# STM32G474RBT6.net
KiCad netlist of a schematic drawn in EasyEDA Pro
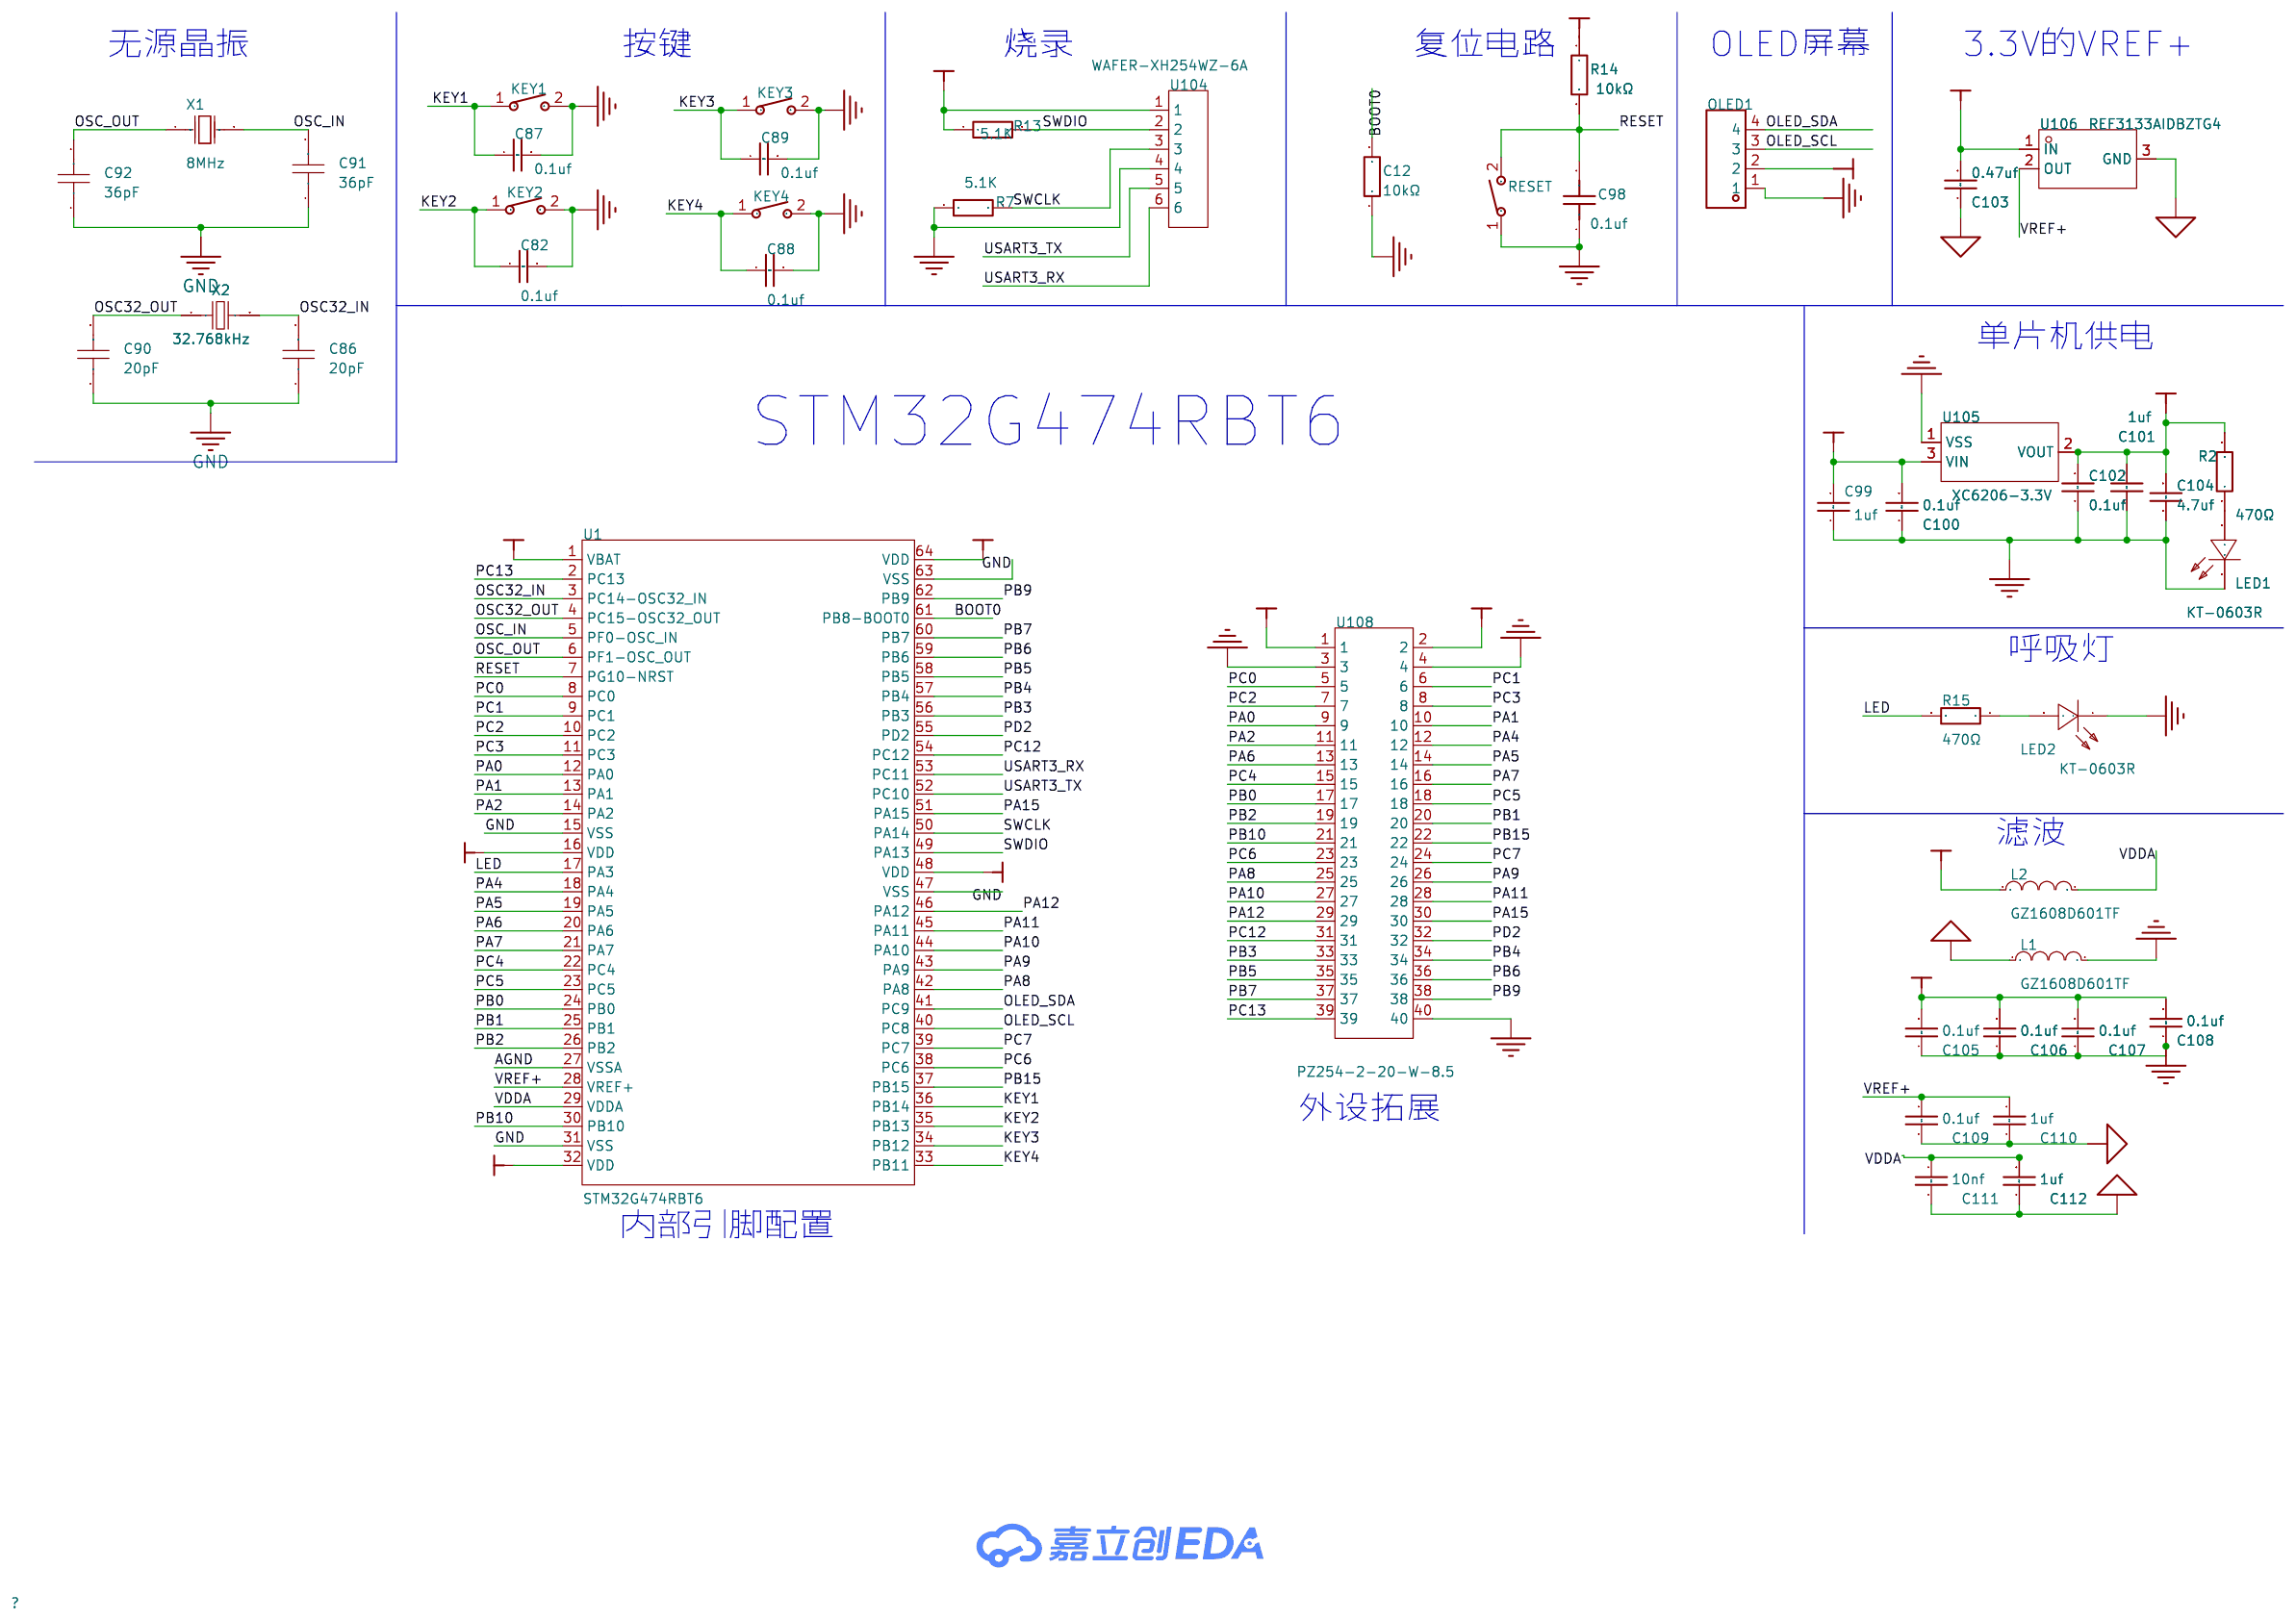
[diagram p0: schematic sheet]

(export (version "E")
  (design (tool "Eeschema 10.0.6"))
  (components
    (comp (ref "C12")
      (value "10kΩ")
      (footprint "easyedapro:R0805")
      (fields
        (field (name "Manufacturer Part") "0805W8F1002T5E")
        (field (name "Manufacturer") "UNI-ROYAL(厚声)")
      )
      (libsource (lib "easyedapro") (part "0805W8F1002T5E"))
    )
    (comp (ref "C82")
      (value "0.1uf")
      (footprint "easyedapro:C0603")
      (libsource (lib "easyedapro") (part "C0603"))
    )
    (comp (ref "C86")
      (value "20pF")
      (footprint "easyedapro:C0603")
      (description "容值:47pF;精度:±5%;额定电压:100V;温度系数:C0G;")
      (fields
        (field (name "Manufacturer Part") "CAI0603C0G470J101JT")
        (field (name "Manufacturer") "HRE(芯声)")
      )
      (libsource (lib "easyedapro") (part "CAI0603C0G470J101JT"))
    )
    (comp (ref "C87")
      (value "0.1uf")
      (footprint "easyedapro:C0603")
      (libsource (lib "easyedapro") (part "C0603"))
    )
    (comp (ref "C88")
      (value "0.1uf")
      (footprint "easyedapro:C0603")
      (libsource (lib "easyedapro") (part "C0603"))
    )
    (comp (ref "C89")
      (value "0.1uf")
      (footprint "easyedapro:C0603")
      (libsource (lib "easyedapro") (part "C0603"))
    )
    (comp (ref "C90")
      (value "20pF")
      (footprint "easyedapro:C0603")
      (description "容值:47pF;精度:±5%;额定电压:100V;温度系数:C0G;")
      (fields
        (field (name "Manufacturer Part") "CAI0603C0G470J101JT")
        (field (name "Manufacturer") "HRE(芯声)")
      )
      (libsource (lib "easyedapro") (part "CAI0603C0G470J101JT"))
    )
    (comp (ref "C91")
      (value "36pF")
      (footprint "easyedapro:C0603")
      (description "容值:47pF;精度:±5%;额定电压:100V;温度系数:C0G;")
      (fields
        (field (name "Manufacturer Part") "CAI0603C0G470J101JT")
        (field (name "Manufacturer") "HRE(芯声)")
      )
      (libsource (lib "easyedapro") (part "CAI0603C0G470J101JT"))
    )
    (comp (ref "C92")
      (value "36pF")
      (footprint "easyedapro:C0603")
      (description "容值:47pF;精度:±5%;额定电压:100V;温度系数:C0G;")
      (fields
        (field (name "Manufacturer Part") "CAI0603C0G470J101JT")
        (field (name "Manufacturer") "HRE(芯声)")
      )
      (libsource (lib "easyedapro") (part "CAI0603C0G470J101JT"))
    )
    (comp (ref "C98") (value "0.1uf") (footprint "easyedapro:电容") (libsource (lib "easyedapro") (part "电容")))
    (comp (ref "C99")
      (value "1uf")
      (footprint "easyedapro:C0603")
      (libsource (lib "easyedapro") (part "C0603"))
    )
    (comp (ref "C100")
      (value "0.1uf")
      (footprint "easyedapro:C0603")
      (libsource (lib "easyedapro") (part "C0603"))
    )
    (comp (ref "C101")
      (value "1uf")
      (footprint "easyedapro:C0603")
      (libsource (lib "easyedapro") (part "C0603"))
    )
    (comp (ref "C102")
      (value "0.1uf")
      (footprint "easyedapro:C0603")
      (libsource (lib "easyedapro") (part "C0603"))
    )
    (comp (ref "C103")
      (value "0.47uf")
      (footprint "easyedapro:C0603")
      (libsource (lib "easyedapro") (part "C0603"))
    )
    (comp (ref "C104")
      (value "4.7uf")
      (footprint "easyedapro:C0603")
      (libsource (lib "easyedapro") (part "C0603"))
    )
    (comp (ref "C105")
      (value "0.1uf")
      (footprint "easyedapro:C0603")
      (libsource (lib "easyedapro") (part "C0603"))
    )
    (comp (ref "C106")
      (value "0.1uf")
      (footprint "easyedapro:C0603")
      (libsource (lib "easyedapro") (part "C0603"))
    )
    (comp (ref "C107")
      (value "0.1uf")
      (footprint "easyedapro:C0603")
      (libsource (lib "easyedapro") (part "C0603"))
    )
    (comp (ref "C108")
      (value "0.1uf")
      (footprint "easyedapro:C0603")
      (libsource (lib "easyedapro") (part "C0603"))
    )
    (comp (ref "C109")
      (value "0.1uf")
      (footprint "easyedapro:C0603")
      (libsource (lib "easyedapro") (part "C0603"))
    )
    (comp (ref "C110")
      (value "1uf")
      (footprint "easyedapro:C0603")
      (libsource (lib "easyedapro") (part "C0603"))
    )
    (comp (ref "C111")
      (value "10nf")
      (footprint "easyedapro:C0603")
      (libsource (lib "easyedapro") (part "C0603"))
    )
    (comp (ref "C112")
      (value "1uf")
      (footprint "easyedapro:C0603")
      (libsource (lib "easyedapro") (part "C0603"))
    )
    (comp (ref "KEY1")
      (value "TS6643WS 250gf 072")
      (footprint "easyedapro:SW-SMD_L6.0-W6.0-P6.00-LS6.8")
      (fields (field (name "Manufacturer") "SHOU HAN(首韩)"))
      (libsource (lib "easyedapro") (part "TS6643WS 250GF 072"))
    )
    (comp (ref "KEY2")
      (value "TS6643WS 250gf 072")
      (footprint "easyedapro:SW-SMD_L6.0-W6.0-P6.00-LS6.8")
      (fields (field (name "Manufacturer") "SHOU HAN(首韩)"))
      (libsource (lib "easyedapro") (part "TS6643WS 250GF 072"))
    )
    (comp (ref "KEY3")
      (value "TS6643WS 250gf 072")
      (footprint "easyedapro:SW-SMD_L6.0-W6.0-P6.00-LS6.8")
      (fields (field (name "Manufacturer") "SHOU HAN(首韩)"))
      (libsource (lib "easyedapro") (part "TS6643WS 250GF 072"))
    )
    (comp (ref "KEY4")
      (value "TS6643WS 250gf 072")
      (footprint "easyedapro:SW-SMD_L6.0-W6.0-P6.00-LS6.8")
      (fields (field (name "Manufacturer") "SHOU HAN(首韩)"))
      (libsource (lib "easyedapro") (part "TS6643WS 250GF 072"))
    )
    (comp (ref "L1")
      (value "GZ1608D601TF")
      (footprint "easyedapro:L0603")
      (description "阻抗@频率:600Ω@100MHz;误差:±25%;直流电阻(DCR):450mΩ;")
      (fields (field (name "Manufacturer") "Sunlord(顺络)"))
      (libsource (lib "easyedapro") (part "GZ1608D601TF"))
    )
    (comp (ref "L2")
      (value "GZ1608D601TF")
      (footprint "easyedapro:L0603")
      (description "阻抗@频率:600Ω@100MHz;误差:±25%;直流电阻(DCR):450mΩ;")
      (fields (field (name "Manufacturer") "Sunlord(顺络)"))
      (libsource (lib "easyedapro") (part "GZ1608D601TF"))
    )
    (comp (ref "LED1")
      (value "KT-0603R")
      (footprint "easyedapro:LED0603-RD")
      (fields (field (name "Manufacturer") "KENTO"))
      (libsource (lib "easyedapro") (part "KT-0603R"))
    )
    (comp (ref "LED2")
      (value "KT-0603R")
      (footprint "easyedapro:LED0603-RD")
      (fields (field (name "Manufacturer") "KENTO"))
      (libsource (lib "easyedapro") (part "KT-0603R"))
    )
    (comp (ref "OLED1")
      (value "2.54-1*4P母")
      (footprint "easyedapro:HDR-TH_4P-P2.54-V-F")
      (fields (field (name "Manufacturer") "BOOMELE(博穆精密)"))
      (libsource (lib "easyedapro") (part "2.54-1*4P母"))
    )
    (comp (ref "R2")
      (value "470Ω")
      (footprint "easyedapro:R0805")
      (description "电阻类型:厚膜电阻;阻值:5.1kΩ;精度:±1%;功率:125mW;最大工作电压:150V;温度系数:±100ppm/℃;")
      (fields
        (field (name "Manufacturer Part") "0805W8F5101T5E")
        (field (name "Manufacturer") "UNI-ROYAL(厚声)")
      )
      (libsource (lib "easyedapro") (part "0805W8F5101T5E"))
    )
    (comp (ref "R7") (value "5.1K") (footprint "easyedapro:电阻") (libsource (lib "easyedapro") (part "电阻")))
    (comp (ref "R13") (value "5.1K") (footprint "easyedapro:电阻") (libsource (lib "easyedapro") (part "电阻")))
    (comp (ref "R14") (value "10kΩ") (footprint "easyedapro:电阻") (libsource (lib "easyedapro") (part "电阻")))
    (comp (ref "R15")
      (value "470Ω")
      (footprint "easyedapro:R0805")
      (description "电阻类型:厚膜电阻;阻值:5.1kΩ;精度:±1%;功率:125mW;最大工作电压:150V;温度系数:±100ppm/℃;")
      (fields
        (field (name "Manufacturer Part") "0805W8F5101T5E")
        (field (name "Manufacturer") "UNI-ROYAL(厚声)")
      )
      (libsource (lib "easyedapro") (part "0805W8F5101T5E"))
    )
    (comp (ref "RESET")
      (value "TS6643WS 250gf 072")
      (footprint "easyedapro:SW-SMD_L6.0-W6.0-P6.00-LS6.8")
      (fields (field (name "Manufacturer") "SHOU HAN(首韩)"))
      (libsource (lib "easyedapro") (part "TS6643WS 250GF 072"))
    )
    (comp (ref "U1")
      (value "STM32G474RBT6")
      (footprint "easyedapro:LQFP-64_L10.0-W10.0-P0.50-LS12.0-BL")
      (description "CPU内核:ARM-M4;CPU最大主频:170MHz;应用领域:-;")
      (fields (field (name "Manufacturer") "ST(意法半导体)"))
      (libsource (lib "easyedapro") (part "STM32G474RBT6"))
    )
    (comp (ref "U104")
      (value "WAFER-XH254WZ-6A")
      (footprint "easyedapro:CONN-TH_6P-P2.50_WAFER-XH254WZ-6A")
      (description "插针结构:1x6P;间距:2.54mm;安装方式:弯插;参考系列:XH;总PIN数:6P;排数:1;每排PIN数:6;额定电流:3A;触头材质:黄铜;工作温度:-25°C~+85°C;")
      (fields (field (name "Manufacturer") "HANBO(汉博)"))
      (libsource (lib "easyedapro") (part "WAFER-XH254WZ-6A"))
    )
    (comp (ref "U105")
      (value "XC6206-3.3V")
      (footprint "easyedapro:SSOT-3_L2.9-W1.6-P0.95-LS2.8-BR")
      (description "输出类型:固定;工作电压:6V;输出电压:3.3V;输出电流:250mA;电源纹波抑制比(PSRR):-;输出极性:正极;")
      (fields (field (name "Manufacturer") "YONGYUTAI(永裕泰)"))
      (libsource (lib "easyedapro") (part "XC6206-3.3V"))
    )
    (comp (ref "U106")
      (value "REF3133AIDBZTG4")
      (footprint "easyedapro:SOT-23-3_L2.9-W1.4-0.95-LS2.5-BR")
      (description "输出类型:固定;工作电压:3.35V~5.5V;输出电压:3.3V;输出电流:10mA;精度:±0.2%;")
      (fields (field (name "Manufacturer") "TI(德州仪器)"))
      (libsource (lib "easyedapro") (part "REF3133AIDBZTG4"))
    )
    (comp (ref "U108")
      (value "PZ254-2-20-W-8.5")
      (footprint "easyedapro:HDR-TH_40P-P2.54-H-M-R2-C20-S2.54-W12.9-N")
      (fields (field (name "Manufacturer") "HCTL(华灿天禄)"))
      (libsource (lib "easyedapro") (part "PZ254-2-20-W-8.5KK"))
    )
    (comp (ref "X1")
      (value "8MHz")
      (footprint "easyedapro:CRYSTAL-SMD_L5.0-W3.2")
      (description "晶振类型:贴片晶振;频率:8MHz;常温频差:±10ppm;负载电容:20pF;频率稳定度:±20ppm;")
      (fields (field (name "Manufacturer Part") "X50328MSB2GI") (field (name "Manufacturer") "YXC(扬兴晶振)"))
      (libsource (lib "easyedapro") (part "X50328MSB2GI"))
    )
    (comp (ref "X2")
      (value "32.768kHz")
      (footprint "easyedapro:FC-135R_L3.2-W1.5")
      (description "晶振类型:贴片无源晶振;频率:32.768kHz;频率公差:±20ppm;频率稳定度:-;负载电容:12.5pF;等效串联电阻(ESR):70kΩ;工作温度:-40~+85;")
      (fields (field (name "Manufacturer Part") "Q13FC1350000400") (field (name "Manufacturer") "EPSON(爱普生)"))
      (libsource (lib "easyedapro") (part "Q13FC1350000400"))
    )
  )
  (nets
    (net (code "1") (name "/BOOT0") (class "Default")
      (node (ref "C12") (pin "2") (pinfunction "2_2") (pintype "input"))
      (node (ref "U1") (pin "61") (pinfunction "PB8-BOOT0_61") (pintype "unspecified"))
    )
    (net (code "2") (name "/KEY1") (class "Default")
      (node (ref "C87") (pin "1") (pinfunction "1_1") (pintype "input"))
      (node (ref "KEY1") (pin "1") (pinfunction "1_1") (pintype "unspecified"))
      (node (ref "U1") (pin "36") (pinfunction "PB14_36") (pintype "unspecified"))
    )
    (net (code "3") (name "/KEY2") (class "Default")
      (node (ref "C82") (pin "1") (pinfunction "1_1") (pintype "input"))
      (node (ref "KEY2") (pin "1") (pinfunction "1_1") (pintype "unspecified"))
      (node (ref "U1") (pin "35") (pinfunction "PB13_35") (pintype "unspecified"))
    )
    (net (code "4") (name "/KEY3") (class "Default")
      (node (ref "C89") (pin "1") (pinfunction "1_1") (pintype "input"))
      (node (ref "KEY3") (pin "1") (pinfunction "1_1") (pintype "unspecified"))
      (node (ref "U1") (pin "34") (pinfunction "PB12_34") (pintype "unspecified"))
    )
    (net (code "5") (name "/KEY4") (class "Default")
      (node (ref "C88") (pin "1") (pinfunction "1_1") (pintype "input"))
      (node (ref "KEY4") (pin "1") (pinfunction "1_1") (pintype "unspecified"))
      (node (ref "U1") (pin "33") (pinfunction "PB11_33") (pintype "unspecified"))
    )
    (net (code "6") (name "/LED") (class "Default")
      (node (ref "R15") (pin "2") (pinfunction "2_2") (pintype "input"))
      (node (ref "U1") (pin "17") (pinfunction "PA3_17") (pintype "unspecified"))
    )
    (net (code "7") (name "/OLED_SCL") (class "Default")
      (node (ref "OLED1") (pin "3") (pinfunction "3_3") (pintype "unspecified"))
      (node (ref "U1") (pin "40") (pinfunction "PC8_40") (pintype "unspecified"))
    )
    (net (code "8") (name "/OLED_SDA") (class "Default")
      (node (ref "OLED1") (pin "4") (pinfunction "4_4") (pintype "unspecified"))
      (node (ref "U1") (pin "41") (pinfunction "PC9_41") (pintype "unspecified"))
    )
    (net (code "9") (name "/OSC32_IN") (class "Default")
      (node (ref "C86") (pin "2") (pinfunction "2_2") (pintype "unspecified"))
      (node (ref "U1") (pin "3") (pinfunction "PC14-OSC32_IN_3") (pintype "unspecified"))
      (node (ref "X2") (pin "2") (pinfunction "2_2") (pintype "input"))
    )
    (net (code "10") (name "/OSC32_OUT") (class "Default")
      (node (ref "C90") (pin "2") (pinfunction "2_2") (pintype "unspecified"))
      (node (ref "U1") (pin "4") (pinfunction "PC15-OSC32_OUT_4") (pintype "unspecified"))
      (node (ref "X2") (pin "1") (pinfunction "1_1") (pintype "input"))
    )
    (net (code "11") (name "/OSC_IN") (class "Default")
      (node (ref "C91") (pin "2") (pinfunction "2_2") (pintype "unspecified"))
      (node (ref "U1") (pin "5") (pinfunction "PF0-OSC_IN_5") (pintype "unspecified"))
      (node (ref "X1") (pin "2") (pinfunction "OSC2_2") (pintype "input"))
    )
    (net (code "12") (name "/OSC_OUT") (class "Default")
      (node (ref "C92") (pin "2") (pinfunction "2_2") (pintype "unspecified"))
      (node (ref "U1") (pin "6") (pinfunction "PF1-OSC_OUT_6") (pintype "unspecified"))
      (node (ref "X1") (pin "1") (pinfunction "OSC1_1") (pintype "input"))
    )
    (net (code "13") (name "/PA0") (class "Default")
      (node (ref "U1") (pin "12") (pinfunction "PA0_12") (pintype "unspecified"))
      (node (ref "U108") (pin "9") (pinfunction "9_9") (pintype "unspecified"))
    )
    (net (code "14") (name "/PA1") (class "Default")
      (node (ref "U1") (pin "13") (pinfunction "PA1_13") (pintype "unspecified"))
      (node (ref "U108") (pin "10") (pinfunction "10_10") (pintype "unspecified"))
    )
    (net (code "15") (name "/PA2") (class "Default")
      (node (ref "U1") (pin "14") (pinfunction "PA2_14") (pintype "unspecified"))
      (node (ref "U108") (pin "11") (pinfunction "11_11") (pintype "unspecified"))
    )
    (net (code "16") (name "/PA4") (class "Default")
      (node (ref "U1") (pin "18") (pinfunction "PA4_18") (pintype "unspecified"))
      (node (ref "U108") (pin "12") (pinfunction "12_12") (pintype "unspecified"))
    )
    (net (code "17") (name "/PA5") (class "Default")
      (node (ref "U1") (pin "19") (pinfunction "PA5_19") (pintype "unspecified"))
      (node (ref "U108") (pin "14") (pinfunction "14_14") (pintype "unspecified"))
    )
    (net (code "18") (name "/PA6") (class "Default")
      (node (ref "U1") (pin "20") (pinfunction "PA6_20") (pintype "unspecified"))
      (node (ref "U108") (pin "13") (pinfunction "13_13") (pintype "unspecified"))
    )
    (net (code "19") (name "/PA7") (class "Default")
      (node (ref "U1") (pin "21") (pinfunction "PA7_21") (pintype "unspecified"))
      (node (ref "U108") (pin "16") (pinfunction "16_16") (pintype "unspecified"))
    )
    (net (code "20") (name "/PA8") (class "Default")
      (node (ref "U1") (pin "42") (pinfunction "PA8_42") (pintype "unspecified"))
      (node (ref "U108") (pin "25") (pinfunction "25_25") (pintype "unspecified"))
    )
    (net (code "21") (name "/PA9") (class "Default")
      (node (ref "U1") (pin "43") (pinfunction "PA9_43") (pintype "unspecified"))
      (node (ref "U108") (pin "26") (pinfunction "26_26") (pintype "unspecified"))
    )
    (net (code "22") (name "/PA10") (class "Default")
      (node (ref "U1") (pin "44") (pinfunction "PA10_44") (pintype "unspecified"))
      (node (ref "U108") (pin "27") (pinfunction "27_27") (pintype "unspecified"))
    )
    (net (code "23") (name "/PA11") (class "Default")
      (node (ref "U1") (pin "45") (pinfunction "PA11_45") (pintype "unspecified"))
      (node (ref "U108") (pin "28") (pinfunction "28_28") (pintype "unspecified"))
    )
    (net (code "24") (name "/PA12") (class "Default")
      (node (ref "U1") (pin "46") (pinfunction "PA12_46") (pintype "unspecified"))
      (node (ref "U108") (pin "29") (pinfunction "29_29") (pintype "unspecified"))
    )
    (net (code "25") (name "/PA15") (class "Default")
      (node (ref "U1") (pin "51") (pinfunction "PA15_51") (pintype "unspecified"))
      (node (ref "U108") (pin "30") (pinfunction "30_30") (pintype "unspecified"))
    )
    (net (code "26") (name "/PB0") (class "Default")
      (node (ref "U1") (pin "24") (pinfunction "PB0_24") (pintype "unspecified"))
      (node (ref "U108") (pin "17") (pinfunction "17_17") (pintype "unspecified"))
    )
    (net (code "27") (name "/PB1") (class "Default")
      (node (ref "U1") (pin "25") (pinfunction "PB1_25") (pintype "unspecified"))
      (node (ref "U108") (pin "20") (pinfunction "20_20") (pintype "unspecified"))
    )
    (net (code "28") (name "/PB2") (class "Default")
      (node (ref "U1") (pin "26") (pinfunction "PB2_26") (pintype "unspecified"))
      (node (ref "U108") (pin "19") (pinfunction "19_19") (pintype "unspecified"))
    )
    (net (code "29") (name "/PB3") (class "Default")
      (node (ref "U1") (pin "56") (pinfunction "PB3_56") (pintype "unspecified"))
      (node (ref "U108") (pin "33") (pinfunction "33_33") (pintype "unspecified"))
    )
    (net (code "30") (name "/PB4") (class "Default")
      (node (ref "U1") (pin "57") (pinfunction "PB4_57") (pintype "unspecified"))
      (node (ref "U108") (pin "34") (pinfunction "34_34") (pintype "unspecified"))
    )
    (net (code "31") (name "/PB5") (class "Default")
      (node (ref "U1") (pin "58") (pinfunction "PB5_58") (pintype "unspecified"))
      (node (ref "U108") (pin "35") (pinfunction "35_35") (pintype "unspecified"))
    )
    (net (code "32") (name "/PB6") (class "Default")
      (node (ref "U1") (pin "59") (pinfunction "PB6_59") (pintype "unspecified"))
      (node (ref "U108") (pin "36") (pinfunction "36_36") (pintype "unspecified"))
    )
    (net (code "33") (name "/PB7") (class "Default")
      (node (ref "U1") (pin "60") (pinfunction "PB7_60") (pintype "unspecified"))
      (node (ref "U108") (pin "37") (pinfunction "37_37") (pintype "unspecified"))
    )
    (net (code "34") (name "/PB9") (class "Default")
      (node (ref "U1") (pin "62") (pinfunction "PB9_62") (pintype "unspecified"))
      (node (ref "U108") (pin "38") (pinfunction "38_38") (pintype "unspecified"))
    )
    (net (code "35") (name "/PB10") (class "Default")
      (node (ref "U1") (pin "30") (pinfunction "PB10_30") (pintype "unspecified"))
      (node (ref "U108") (pin "21") (pinfunction "21_21") (pintype "unspecified"))
    )
    (net (code "36") (name "/PB15") (class "Default")
      (node (ref "U1") (pin "37") (pinfunction "PB15_37") (pintype "unspecified"))
      (node (ref "U108") (pin "22") (pinfunction "22_22") (pintype "unspecified"))
    )
    (net (code "37") (name "/PC0") (class "Default")
      (node (ref "U1") (pin "8") (pinfunction "PC0_8") (pintype "unspecified"))
      (node (ref "U108") (pin "5") (pinfunction "5_5") (pintype "unspecified"))
    )
    (net (code "38") (name "/PC1") (class "Default")
      (node (ref "U1") (pin "9") (pinfunction "PC1_9") (pintype "unspecified"))
      (node (ref "U108") (pin "6") (pinfunction "6_6") (pintype "unspecified"))
    )
    (net (code "39") (name "/PC2") (class "Default")
      (node (ref "U1") (pin "10") (pinfunction "PC2_10") (pintype "unspecified"))
      (node (ref "U108") (pin "7") (pinfunction "7_7") (pintype "unspecified"))
    )
    (net (code "40") (name "/PC3") (class "Default")
      (node (ref "U1") (pin "11") (pinfunction "PC3_11") (pintype "unspecified"))
      (node (ref "U108") (pin "8") (pinfunction "8_8") (pintype "unspecified"))
    )
    (net (code "41") (name "/PC4") (class "Default")
      (node (ref "U1") (pin "22") (pinfunction "PC4_22") (pintype "unspecified"))
      (node (ref "U108") (pin "15") (pinfunction "15_15") (pintype "unspecified"))
    )
    (net (code "42") (name "/PC5") (class "Default")
      (node (ref "U1") (pin "23") (pinfunction "PC5_23") (pintype "unspecified"))
      (node (ref "U108") (pin "18") (pinfunction "18_18") (pintype "unspecified"))
    )
    (net (code "43") (name "/PC6") (class "Default")
      (node (ref "U1") (pin "38") (pinfunction "PC6_38") (pintype "unspecified"))
      (node (ref "U108") (pin "23") (pinfunction "23_23") (pintype "unspecified"))
    )
    (net (code "44") (name "/PC7") (class "Default")
      (node (ref "U1") (pin "39") (pinfunction "PC7_39") (pintype "unspecified"))
      (node (ref "U108") (pin "24") (pinfunction "24_24") (pintype "unspecified"))
    )
    (net (code "45") (name "/PC12") (class "Default")
      (node (ref "U1") (pin "54") (pinfunction "PC12_54") (pintype "unspecified"))
      (node (ref "U108") (pin "31") (pinfunction "31_31") (pintype "unspecified"))
    )
    (net (code "46") (name "/PC13") (class "Default")
      (node (ref "U1") (pin "2") (pinfunction "PC13_2") (pintype "unspecified"))
      (node (ref "U108") (pin "39") (pinfunction "39_39") (pintype "unspecified"))
    )
    (net (code "47") (name "/PD2") (class "Default")
      (node (ref "U1") (pin "55") (pinfunction "PD2_55") (pintype "unspecified"))
      (node (ref "U108") (pin "32") (pinfunction "32_32") (pintype "unspecified"))
    )
    (net (code "48") (name "/RESET") (class "Default")
      (node (ref "C98") (pin "2") (pinfunction "2_2") (pintype "input"))
      (node (ref "R14") (pin "2") (pinfunction "2_2") (pintype "input"))
      (node (ref "RESET") (pin "2") (pinfunction "2_2") (pintype "unspecified"))
      (node (ref "U1") (pin "7") (pinfunction "PG10-NRST_7") (pintype "unspecified"))
    )
    (net (code "49") (name "/SWCLK") (class "Default")
      (node (ref "R7") (pin "2") (pinfunction "2_2") (pintype "input"))
      (node (ref "U1") (pin "50") (pinfunction "PA14_50") (pintype "unspecified"))
      (node (ref "U104") (pin "3") (pinfunction "3_3") (pintype "unspecified"))
    )
    (net (code "50") (name "/SWDIO") (class "Default")
      (node (ref "R13") (pin "2") (pinfunction "2_2") (pintype "input"))
      (node (ref "U1") (pin "49") (pinfunction "PA13_49") (pintype "unspecified"))
      (node (ref "U104") (pin "2") (pinfunction "2_2") (pintype "unspecified"))
    )
    (net (code "51") (name "/USART3_RX") (class "Default")
      (node (ref "U1") (pin "53") (pinfunction "PC11_53") (pintype "unspecified"))
      (node (ref "U104") (pin "6") (pinfunction "6_6") (pintype "unspecified"))
    )
    (net (code "52") (name "/USART3_TX") (class "Default")
      (node (ref "U1") (pin "52") (pinfunction "PC10_52") (pintype "unspecified"))
      (node (ref "U104") (pin "5") (pinfunction "5_5") (pintype "unspecified"))
    )
    (net (code "53") (name "/VDDA") (class "Default")
      (node (ref "C111") (pin "2") (pinfunction "2_2") (pintype "input"))
      (node (ref "C112") (pin "2") (pinfunction "2_2") (pintype "input"))
      (node (ref "L2") (pin "2") (pinfunction "2_2") (pintype "unspecified"))
      (node (ref "U1") (pin "29") (pinfunction "VDDA_29") (pintype "unspecified"))
    )
    (net (code "54") (name "/VREF+") (class "Default")
      (node (ref "C109") (pin "2") (pinfunction "2_2") (pintype "input"))
      (node (ref "C110") (pin "2") (pinfunction "2_2") (pintype "input"))
      (node (ref "U1") (pin "28") (pinfunction "VREF+_28") (pintype "unspecified"))
      (node (ref "U106") (pin "2") (pinfunction "OUT_2") (pintype "unspecified"))
    )
    (net (code "55") (name "3V3") (class "Default")
      (node (ref "C101") (pin "2") (pinfunction "2_2") (pintype "input"))
      (node (ref "C102") (pin "2") (pinfunction "2_2") (pintype "input"))
      (node (ref "C104") (pin "2") (pinfunction "2_2") (pintype "input"))
      (node (ref "C105") (pin "2") (pinfunction "2_2") (pintype "input"))
      (node (ref "C106") (pin "2") (pinfunction "2_2") (pintype "input"))
      (node (ref "C107") (pin "2") (pinfunction "2_2") (pintype "input"))
      (node (ref "C108") (pin "2") (pinfunction "2_2") (pintype "input"))
      (node (ref "L2") (pin "1") (pinfunction "1_1") (pintype "unspecified"))
      (node (ref "OLED1") (pin "2") (pinfunction "2_2") (pintype "unspecified"))
      (node (ref "R13") (pin "1") (pinfunction "1_1") (pintype "input"))
      (node (ref "R14") (pin "1") (pinfunction "1_1") (pintype "input"))
      (node (ref "R2") (pin "2") (pinfunction "2_2") (pintype "input"))
      (node (ref "U1") (pin "1") (pinfunction "VBAT_1") (pintype "unspecified"))
      (node (ref "U1") (pin "16") (pinfunction "VDD_16") (pintype "unspecified"))
      (node (ref "U1") (pin "32") (pinfunction "VDD_32") (pintype "unspecified"))
      (node (ref "U1") (pin "48") (pinfunction "VDD_48") (pintype "unspecified"))
      (node (ref "U1") (pin "64") (pinfunction "VDD_64") (pintype "unspecified"))
      (node (ref "U104") (pin "1") (pinfunction "1_1") (pintype "unspecified"))
      (node (ref "U105") (pin "2") (pinfunction "VOUT_2") (pintype "unspecified"))
    )
    (net (code "56") (name "5V") (class "Default")
      (node (ref "C100") (pin "2") (pinfunction "2_2") (pintype "input"))
      (node (ref "C103") (pin "2") (pinfunction "2_2") (pintype "input"))
      (node (ref "C99") (pin "2") (pinfunction "2_2") (pintype "input"))
      (node (ref "U105") (pin "3") (pinfunction "VIN_3") (pintype "unspecified"))
      (node (ref "U106") (pin "1") (pinfunction "IN_1") (pintype "unspecified"))
      (node (ref "U108") (pin "1") (pinfunction "1_1") (pintype "unspecified"))
      (node (ref "U108") (pin "2") (pinfunction "2_2") (pintype "unspecified"))
    )
    (net (code "57") (name "AGND") (class "Default")
      (node (ref "C103") (pin "1") (pinfunction "1_1") (pintype "input"))
      (node (ref "C109") (pin "1") (pinfunction "1_1") (pintype "input"))
      (node (ref "C110") (pin "1") (pinfunction "1_1") (pintype "input"))
      (node (ref "C111") (pin "1") (pinfunction "1_1") (pintype "input"))
      (node (ref "C112") (pin "1") (pinfunction "1_1") (pintype "input"))
      (node (ref "L1") (pin "1") (pinfunction "1_1") (pintype "unspecified"))
      (node (ref "U1") (pin "27") (pinfunction "VSSA_27") (pintype "unspecified"))
      (node (ref "U106") (pin "3") (pinfunction "GND_3") (pintype "unspecified"))
    )
    (net (code "58") (name "GND") (class "Default")
      (node (ref "C100") (pin "1") (pinfunction "1_1") (pintype "input"))
      (node (ref "C101") (pin "1") (pinfunction "1_1") (pintype "input"))
      (node (ref "C102") (pin "1") (pinfunction "1_1") (pintype "input"))
      (node (ref "C104") (pin "1") (pinfunction "1_1") (pintype "input"))
      (node (ref "C105") (pin "1") (pinfunction "1_1") (pintype "input"))
      (node (ref "C106") (pin "1") (pinfunction "1_1") (pintype "input"))
      (node (ref "C107") (pin "1") (pinfunction "1_1") (pintype "input"))
      (node (ref "C108") (pin "1") (pinfunction "1_1") (pintype "input"))
      (node (ref "C12") (pin "1") (pinfunction "1_1") (pintype "input"))
      (node (ref "C82") (pin "2") (pinfunction "2_2") (pintype "input"))
      (node (ref "C86") (pin "1") (pinfunction "1_1") (pintype "unspecified"))
      (node (ref "C87") (pin "2") (pinfunction "2_2") (pintype "input"))
      (node (ref "C88") (pin "2") (pinfunction "2_2") (pintype "input"))
      (node (ref "C89") (pin "2") (pinfunction "2_2") (pintype "input"))
      (node (ref "C90") (pin "1") (pinfunction "1_1") (pintype "unspecified"))
      (node (ref "C91") (pin "1") (pinfunction "1_1") (pintype "unspecified"))
      (node (ref "C92") (pin "1") (pinfunction "1_1") (pintype "unspecified"))
      (node (ref "C98") (pin "1") (pinfunction "1_1") (pintype "input"))
      (node (ref "C99") (pin "1") (pinfunction "1_1") (pintype "input"))
      (node (ref "KEY1") (pin "2") (pinfunction "2_2") (pintype "unspecified"))
      (node (ref "KEY2") (pin "2") (pinfunction "2_2") (pintype "unspecified"))
      (node (ref "KEY3") (pin "2") (pinfunction "2_2") (pintype "unspecified"))
      (node (ref "KEY4") (pin "2") (pinfunction "2_2") (pintype "unspecified"))
      (node (ref "L1") (pin "2") (pinfunction "2_2") (pintype "unspecified"))
      (node (ref "LED1") (pin "1") (pinfunction "K_1") (pintype "unspecified"))
      (node (ref "LED2") (pin "1") (pinfunction "K_1") (pintype "unspecified"))
      (node (ref "OLED1") (pin "1") (pinfunction "1_1") (pintype "unspecified"))
      (node (ref "R7") (pin "1") (pinfunction "1_1") (pintype "input"))
      (node (ref "RESET") (pin "1") (pinfunction "1_1") (pintype "unspecified"))
      (node (ref "U1") (pin "15") (pinfunction "VSS_15") (pintype "unspecified"))
      (node (ref "U1") (pin "31") (pinfunction "VSS_31") (pintype "unspecified"))
      (node (ref "U1") (pin "47") (pinfunction "VSS_47") (pintype "unspecified"))
      (node (ref "U1") (pin "63") (pinfunction "VSS_63") (pintype "unspecified"))
      (node (ref "U104") (pin "4") (pinfunction "4_4") (pintype "unspecified"))
      (node (ref "U105") (pin "1") (pinfunction "VSS_1") (pintype "unspecified"))
      (node (ref "U108") (pin "3") (pinfunction "3_3") (pintype "unspecified"))
      (node (ref "U108") (pin "4") (pinfunction "4_4") (pintype "unspecified"))
      (node (ref "U108") (pin "40") (pinfunction "40_40") (pintype "unspecified"))
    )
    (net (code "59") (name "Net-(LED1-A)") (class "Default")
      (node (ref "LED1") (pin "2") (pinfunction "A_2") (pintype "unspecified"))
      (node (ref "R2") (pin "1") (pinfunction "1_1") (pintype "input"))
    )
    (net (code "60") (name "Net-(LED2-A)") (class "Default")
      (node (ref "LED2") (pin "2") (pinfunction "A_2") (pintype "unspecified"))
      (node (ref "R15") (pin "1") (pinfunction "1_1") (pintype "input"))
    )
  )
)
